# linetracer.net
KiCad netlist of a schematic drawn in EAGLE
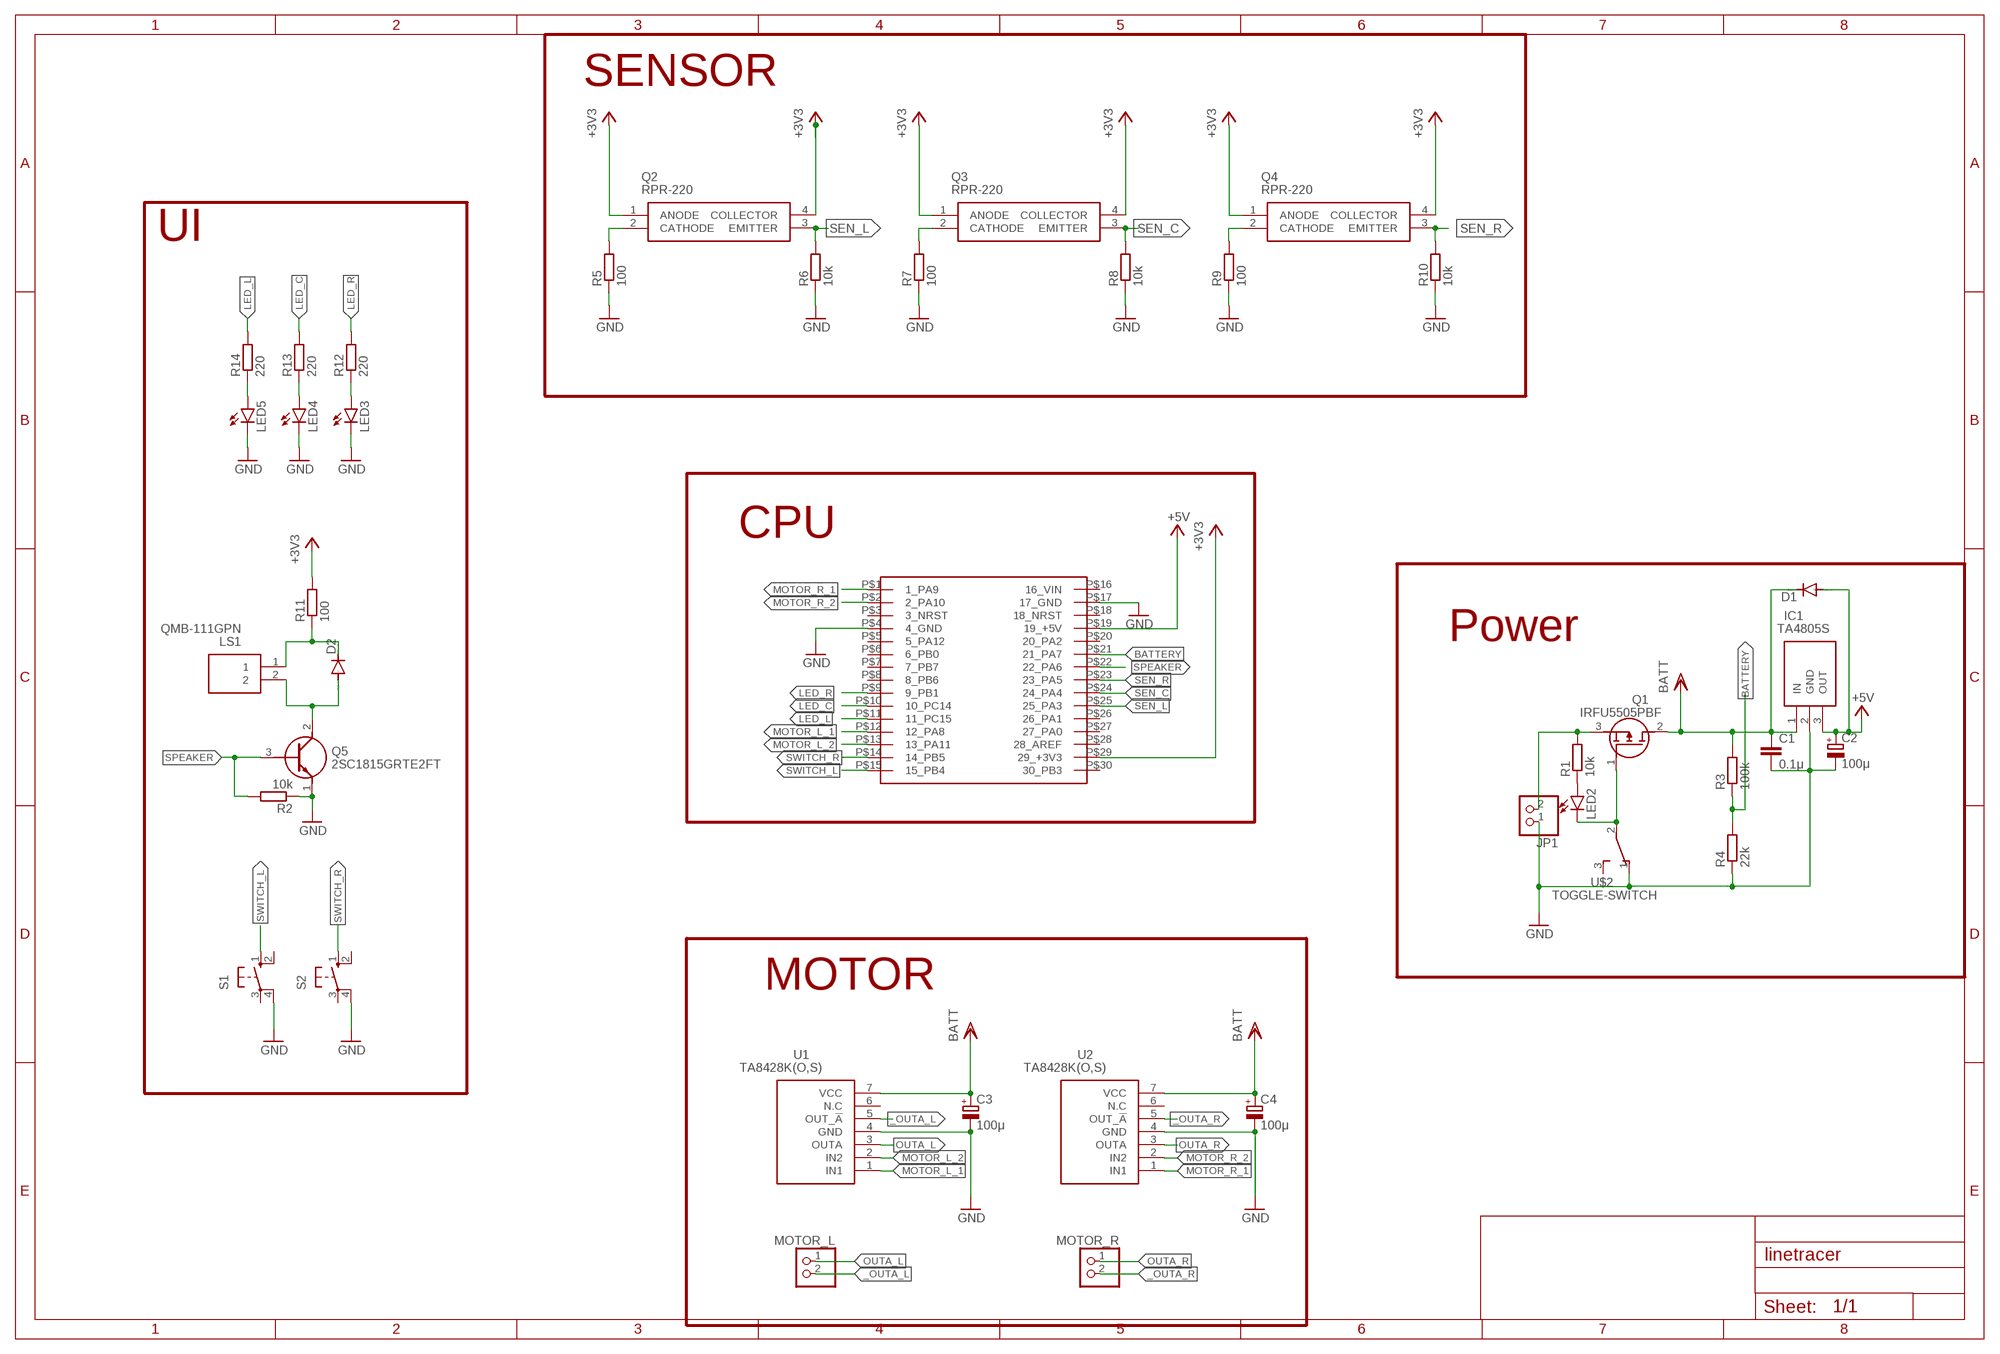
[diagram p0: schematic, sheet 1]

(export (version "E")
  (design (tool "Eeschema 10.0.6"))
  (components
    (comp (ref "C1")
      (value "0.1μ")
      (footprint "eagle-import:C025-024X044")
      (libsource (lib "eagle-import") (part "C-EU025-024X044"))
    )
    (comp (ref "C2")
      (value "100μ")
      (footprint "eagle-import:E2,5-7")
      (libsource (lib "eagle-import") (part "CPOL-EUE2.5-7"))
    )
    (comp (ref "C3")
      (value "100μ")
      (footprint "eagle-import:E2,5-7")
      (libsource (lib "eagle-import") (part "CPOL-EUE2.5-7"))
    )
    (comp (ref "C4")
      (value "100μ")
      (footprint "eagle-import:E2,5-7")
      (libsource (lib "eagle-import") (part "CPOL-EUE2.5-7"))
    )
    (comp (ref "D1")
      (value "DIODE-D-2.5")
      (footprint "eagle-import:D-2.5")
      (libsource (lib "eagle-import") (part "DIODE-D-2.5"))
    )
    (comp (ref "D2")
      (value "DIODE-D-2.5")
      (footprint "eagle-import:D-2.5")
      (libsource (lib "eagle-import") (part "DIODE-D-2.5"))
    )
    (comp (ref "IC1")
      (value "TA4805S")
      (footprint "eagle-import:TO230P250X680X1080-3P")
      (fields (field (name "MANUFACTURER_PART_NUMBER") "TA4805F"))
      (libsource (lib "eagle-import") (part "TA4805S"))
    )
    (comp (ref "JP1")
      (value "PINHD-1X2")
      (footprint "eagle-import:1X02")
      (libsource (lib "eagle-import") (part "PINHD-1X2"))
    )
    (comp (ref "LED2")
      (value "LED3MM")
      (footprint "eagle-import:LED3MM")
      (libsource (lib "eagle-import") (part "LED3MM"))
    )
    (comp (ref "LED3")
      (value "LED3MM")
      (footprint "eagle-import:LED3MM")
      (libsource (lib "eagle-import") (part "LED3MM"))
    )
    (comp (ref "LED4")
      (value "LED3MM")
      (footprint "eagle-import:LED3MM")
      (libsource (lib "eagle-import") (part "LED3MM"))
    )
    (comp (ref "LED5")
      (value "LED3MM")
      (footprint "eagle-import:LED3MM")
      (libsource (lib "eagle-import") (part "LED3MM"))
    )
    (comp (ref "LS1")
      (value "QMB-111GPN")
      (footprint "eagle-import:QMB111GPN")
      (libsource (lib "eagle-import") (part "QMB-111GPN"))
    )
    (comp (ref "MOTOR_L")
      (value "PINHD-1X2")
      (footprint "eagle-import:1X02")
      (libsource (lib "eagle-import") (part "pinhead_325_PINHD-1X2"))
    )
    (comp (ref "MOTOR_R")
      (value "PINHD-1X2")
      (footprint "eagle-import:1X02")
      (libsource (lib "eagle-import") (part "pinhead_325_PINHD-1X2"))
    )
    (comp (ref "Q1")
      (value "IRFU5505PBF")
      (footprint "eagle-import:TO229P239X654X978-3P")
      (fields (field (name "MOUSER_PART_NUMBER") "942-IRFU5505PBF"))
      (libsource (lib "eagle-import") (part "IRFU5505PBF"))
    )
    (comp (ref "Q2")
      (value "RPR-220")
      (footprint "eagle-import:RPR-220")
      (fields (field (name "MOUSER_PART_NUMBER") "755-RPR-220") (field (name "RS_PART_NUMBER") "1246800P"))
      (libsource (lib "eagle-import") (part "RPR-220"))
    )
    (comp (ref "Q3")
      (value "RPR-220")
      (footprint "eagle-import:RPR-220")
      (fields (field (name "MOUSER_PART_NUMBER") "755-RPR-220") (field (name "RS_PART_NUMBER") "1246800P"))
      (libsource (lib "eagle-import") (part "RPR-220"))
    )
    (comp (ref "Q4")
      (value "RPR-220")
      (footprint "eagle-import:RPR-220")
      (fields (field (name "MOUSER_PART_NUMBER") "755-RPR-220") (field (name "RS_PART_NUMBER") "1246800P"))
      (libsource (lib "eagle-import") (part "RPR-220"))
    )
    (comp (ref "Q5")
      (value "2SC1815GRTE2FT")
      (footprint "eagle-import:2-5F1B")
      (fields (field (name "MOUSER_PART_NUMBER") "757-2SC1815GRTE2FT"))
      (libsource (lib "eagle-import") (part "2SC1815GRTE2FT"))
    )
    (comp (ref "R1")
      (value "10k")
      (footprint "eagle-import:0204V")
      (libsource (lib "eagle-import") (part "R-EU_0204/2V"))
    )
    (comp (ref "R2")
      (value "10k")
      (footprint "eagle-import:0204V")
      (libsource (lib "eagle-import") (part "R-EU_0204/2V"))
    )
    (comp (ref "R3")
      (value "100k")
      (footprint "eagle-import:0204V")
      (libsource (lib "eagle-import") (part "R-EU_0204/2V"))
    )
    (comp (ref "R4")
      (value "22k")
      (footprint "eagle-import:0204V")
      (libsource (lib "eagle-import") (part "R-EU_0204/2V"))
    )
    (comp (ref "R5")
      (value "100")
      (footprint "eagle-import:0204V")
      (libsource (lib "eagle-import") (part "R-EU_0204/2V"))
    )
    (comp (ref "R6")
      (value "10k")
      (footprint "eagle-import:0204V")
      (libsource (lib "eagle-import") (part "R-EU_0204/2V"))
    )
    (comp (ref "R7")
      (value "100")
      (footprint "eagle-import:0204V")
      (libsource (lib "eagle-import") (part "R-EU_0204/2V"))
    )
    (comp (ref "R8")
      (value "10k")
      (footprint "eagle-import:0204V")
      (libsource (lib "eagle-import") (part "R-EU_0204/2V"))
    )
    (comp (ref "R9")
      (value "100")
      (footprint "eagle-import:0204V")
      (libsource (lib "eagle-import") (part "R-EU_0204/2V"))
    )
    (comp (ref "R10")
      (value "10k")
      (footprint "eagle-import:0204V")
      (libsource (lib "eagle-import") (part "R-EU_0204/2V"))
    )
    (comp (ref "R11")
      (value "100")
      (footprint "eagle-import:0204V")
      (libsource (lib "eagle-import") (part "R-EU_0204/2V"))
    )
    (comp (ref "R12")
      (value "220")
      (footprint "eagle-import:0204V")
      (libsource (lib "eagle-import") (part "R-EU_0204/2V"))
    )
    (comp (ref "R13")
      (value "220")
      (footprint "eagle-import:0204V")
      (libsource (lib "eagle-import") (part "R-EU_0204/2V"))
    )
    (comp (ref "R14")
      (value "220")
      (footprint "eagle-import:0204V")
      (libsource (lib "eagle-import") (part "R-EU_0204/2V"))
    )
    (comp (ref "S1")
      (value "10-XX")
      (footprint "eagle-import:B3F-10XX")
      (fields (field (name "MPN") "B3F-1000"))
      (libsource (lib "eagle-import") (part "10-XX"))
    )
    (comp (ref "S2")
      (value "10-XX")
      (footprint "eagle-import:B3F-10XX")
      (fields (field (name "MPN") "B3F-1000"))
      (libsource (lib "eagle-import") (part "10-XX"))
    )
    (comp (ref "U$1")
      (value "NUCLEO_L432KC")
      (footprint "eagle-import:NUCLEO_L432KC")
      (libsource (lib "eagle-import") (part "NUCLEO_L432KC"))
    )
    (comp (ref "U$2")
      (value "TOGGLE-SWITCH")
      (footprint "eagle-import:1X03")
      (libsource (lib "eagle-import") (part "TOGGLE-SWITCH"))
    )
    (comp (ref "U1")
      (value "TA8428K(O,S)")
      (footprint "eagle-import:HSIP7-P-2.54_1")
      (fields (field (name "MOUSER_PART_NUMBER") "757-TA8428KOS") (field (name "RS_PART_NUMBER") "6939336"))
      (libsource (lib "eagle-import") (part "TA8428K(O,S)"))
    )
    (comp (ref "U2")
      (value "TA8428K(O,S)")
      (footprint "eagle-import:HSIP7-P-2.54_1")
      (fields (field (name "MOUSER_PART_NUMBER") "757-TA8428KOS") (field (name "RS_PART_NUMBER") "6939336"))
      (libsource (lib "eagle-import") (part "TA8428K(O,S)"))
    )
  )
  (nets
    (net (code "1") (name "+3V3") (class "Default")
      (node (ref "Q2") (pin "1") (pinfunction "ANODE_1") (pintype "bidirectional"))
      (node (ref "Q2") (pin "4") (pinfunction "COLLECTOR_4") (pintype "bidirectional"))
      (node (ref "Q3") (pin "1") (pinfunction "ANODE_1") (pintype "bidirectional"))
      (node (ref "Q3") (pin "4") (pinfunction "COLLECTOR_4") (pintype "bidirectional"))
      (node (ref "Q4") (pin "1") (pinfunction "ANODE_1") (pintype "bidirectional"))
      (node (ref "Q4") (pin "4") (pinfunction "COLLECTOR_4") (pintype "bidirectional"))
      (node (ref "R11") (pin "2") (pinfunction "2_2") (pintype "passive"))
      (node (ref "U$1") (pin "P$29") (pinfunction "29_+3V3_P$29") (pintype "power_in"))
    )
    (net (code "2") (name "+5V") (class "Default")
      (node (ref "C2") (pin "+") (pinfunction "+_+") (pintype "passive"))
      (node (ref "D1") (pin "A") (pinfunction "A_A") (pintype "passive"))
      (node (ref "IC1") (pin "3") (pinfunction "OUT_3") (pintype "bidirectional"))
      (node (ref "U$1") (pin "P$19") (pinfunction "19_+5V_P$19") (pintype "power_in"))
    )
    (net (code "3") (name "/16_VIN") (class "Default")
      (node (ref "U$1") (pin "P$16") (pinfunction "16_VIN_P$16") (pintype "power_in"))
    )
    (net (code "4") (name "BATT") (class "Default")
      (node (ref "C1") (pin "1") (pinfunction "1_1") (pintype "passive"))
      (node (ref "C3") (pin "+") (pinfunction "+_+") (pintype "passive"))
      (node (ref "C4") (pin "+") (pinfunction "+_+") (pintype "passive"))
      (node (ref "D1") (pin "C") (pinfunction "C_C") (pintype "passive"))
      (node (ref "IC1") (pin "1") (pinfunction "IN_1") (pintype "bidirectional"))
      (node (ref "Q1") (pin "2") (pinfunction "D_2") (pintype "bidirectional"))
      (node (ref "R3") (pin "2") (pinfunction "2_2") (pintype "passive"))
      (node (ref "U1") (pin "7") (pinfunction "VCC_7") (pintype "bidirectional"))
      (node (ref "U2") (pin "7") (pinfunction "VCC_7") (pintype "bidirectional"))
    )
    (net (code "5") (name "BATTERY") (class "Default")
      (node (ref "R3") (pin "1") (pinfunction "1_1") (pintype "passive"))
      (node (ref "R4") (pin "2") (pinfunction "2_2") (pintype "passive"))
      (node (ref "U$1") (pin "P$21") (pinfunction "21_PA7_P$21") (pintype "bidirectional"))
    )
    (net (code "6") (name "GND") (class "Default")
      (node (ref "C1") (pin "2") (pinfunction "2_2") (pintype "passive"))
      (node (ref "C2") (pin "-") (pinfunction "-_-") (pintype "passive"))
      (node (ref "C3") (pin "-") (pinfunction "-_-") (pintype "passive"))
      (node (ref "C4") (pin "-") (pinfunction "-_-") (pintype "passive"))
      (node (ref "IC1") (pin "2") (pinfunction "GND_2") (pintype "bidirectional"))
      (node (ref "JP1") (pin "1") (pinfunction "1_1") (pintype "passive"))
      (node (ref "LED3") (pin "K") (pinfunction "C_K") (pintype "passive"))
      (node (ref "LED4") (pin "K") (pinfunction "C_K") (pintype "passive"))
      (node (ref "LED5") (pin "K") (pinfunction "C_K") (pintype "passive"))
      (node (ref "Q5") (pin "1") (pinfunction "E_1") (pintype "bidirectional"))
      (node (ref "R10") (pin "1") (pinfunction "1_1") (pintype "passive"))
      (node (ref "R2") (pin "1") (pinfunction "1_1") (pintype "passive"))
      (node (ref "R4") (pin "1") (pinfunction "1_1") (pintype "passive"))
      (node (ref "R5") (pin "1") (pinfunction "1_1") (pintype "passive"))
      (node (ref "R6") (pin "1") (pinfunction "1_1") (pintype "passive"))
      (node (ref "R7") (pin "1") (pinfunction "1_1") (pintype "passive"))
      (node (ref "R8") (pin "1") (pinfunction "1_1") (pintype "passive"))
      (node (ref "R9") (pin "1") (pinfunction "1_1") (pintype "passive"))
      (node (ref "S1") (pin "4") (pinfunction "P1_4") (pintype "passive"))
      (node (ref "S2") (pin "4") (pinfunction "P1_4") (pintype "passive"))
      (node (ref "U$1") (pin "P$17") (pinfunction "17_GND_P$17") (pintype "power_in"))
      (node (ref "U$1") (pin "P$4") (pinfunction "4_GND_P$4") (pintype "power_in"))
      (node (ref "U$2") (pin "1") (pinfunction "1_1") (pintype "power_in"))
      (node (ref "U1") (pin "4") (pinfunction "GND_4") (pintype "bidirectional"))
      (node (ref "U2") (pin "4") (pinfunction "GND_4") (pintype "bidirectional"))
    )
    (net (code "7") (name "LED_C") (class "Default")
      (node (ref "R13") (pin "2") (pinfunction "2_2") (pintype "passive"))
      (node (ref "U$1") (pin "P$10") (pinfunction "10_PC14_P$10") (pintype "bidirectional"))
    )
    (net (code "8") (name "LED_L") (class "Default")
      (node (ref "R14") (pin "2") (pinfunction "2_2") (pintype "passive"))
      (node (ref "U$1") (pin "P$11") (pinfunction "11_PC15_P$11") (pintype "bidirectional"))
    )
    (net (code "9") (name "LED_R") (class "Default")
      (node (ref "R12") (pin "2") (pinfunction "2_2") (pintype "passive"))
      (node (ref "U$1") (pin "P$9") (pinfunction "9_PB1_P$9") (pintype "bidirectional"))
    )
    (net (code "10") (name "MOTOR_L_1") (class "Default")
      (node (ref "U$1") (pin "P$12") (pinfunction "12_PA8_P$12") (pintype "bidirectional"))
      (node (ref "U1") (pin "1") (pinfunction "IN1_1") (pintype "bidirectional"))
    )
    (net (code "11") (name "MOTOR_L_2") (class "Default")
      (node (ref "U$1") (pin "P$13") (pinfunction "13_PA11_P$13") (pintype "bidirectional"))
      (node (ref "U1") (pin "2") (pinfunction "IN2_2") (pintype "bidirectional"))
    )
    (net (code "12") (name "MOTOR_R_1") (class "Default")
      (node (ref "U$1") (pin "P$1") (pinfunction "1_PA9_P$1") (pintype "bidirectional"))
      (node (ref "U2") (pin "1") (pinfunction "IN1_1") (pintype "bidirectional"))
    )
    (net (code "13") (name "MOTOR_R_2") (class "Default")
      (node (ref "U$1") (pin "P$2") (pinfunction "2_PA10_P$2") (pintype "bidirectional"))
      (node (ref "U2") (pin "2") (pinfunction "IN2_2") (pintype "bidirectional"))
    )
    (net (code "14") (name "Net-(D2-PadC)") (class "Default")
      (node (ref "D2") (pin "C") (pinfunction "C_C") (pintype "passive"))
      (node (ref "LS1") (pin "1") (pinfunction "1_1") (pintype "bidirectional"))
      (node (ref "R11") (pin "1") (pinfunction "1_1") (pintype "passive"))
    )
    (net (code "15") (name "Net-(LED2-C)") (class "Default")
      (node (ref "LED2") (pin "K") (pinfunction "C_K") (pintype "passive"))
      (node (ref "Q1") (pin "1") (pinfunction "G_1") (pintype "bidirectional"))
      (node (ref "U$2") (pin "2") (pinfunction "2_2") (pintype "passive"))
    )
    (net (code "16") (name "Net-(LED2-PadA)") (class "Default")
      (node (ref "LED2") (pin "A") (pinfunction "A_A") (pintype "passive"))
      (node (ref "R1") (pin "1") (pinfunction "1_1") (pintype "passive"))
    )
    (net (code "17") (name "Net-(LED3-PadA)") (class "Default")
      (node (ref "LED3") (pin "A") (pinfunction "A_A") (pintype "passive"))
      (node (ref "R12") (pin "1") (pinfunction "1_1") (pintype "passive"))
    )
    (net (code "18") (name "Net-(LED4-PadA)") (class "Default")
      (node (ref "LED4") (pin "A") (pinfunction "A_A") (pintype "passive"))
      (node (ref "R13") (pin "1") (pinfunction "1_1") (pintype "passive"))
    )
    (net (code "19") (name "Net-(LED5-PadA)") (class "Default")
      (node (ref "LED5") (pin "A") (pinfunction "A_A") (pintype "passive"))
      (node (ref "R14") (pin "1") (pinfunction "1_1") (pintype "passive"))
    )
    (net (code "20") (name "Net-(Q1-S)") (class "Default")
      (node (ref "JP1") (pin "2") (pinfunction "2_2") (pintype "passive"))
      (node (ref "Q1") (pin "3") (pinfunction "S_3") (pintype "bidirectional"))
      (node (ref "R1") (pin "2") (pinfunction "2_2") (pintype "passive"))
    )
    (net (code "21") (name "Net-(Q2-CATHODE)") (class "Default")
      (node (ref "Q2") (pin "2") (pinfunction "CATHODE_2") (pintype "bidirectional"))
      (node (ref "R5") (pin "2") (pinfunction "2_2") (pintype "passive"))
    )
    (net (code "22") (name "Net-(Q3-CATHODE)") (class "Default")
      (node (ref "Q3") (pin "2") (pinfunction "CATHODE_2") (pintype "bidirectional"))
      (node (ref "R7") (pin "2") (pinfunction "2_2") (pintype "passive"))
    )
    (net (code "23") (name "Net-(Q4-CATHODE)") (class "Default")
      (node (ref "Q4") (pin "2") (pinfunction "CATHODE_2") (pintype "bidirectional"))
      (node (ref "R9") (pin "2") (pinfunction "2_2") (pintype "passive"))
    )
    (net (code "24") (name "Net-(Q5-C)") (class "Default")
      (node (ref "D2") (pin "A") (pinfunction "A_A") (pintype "passive"))
      (node (ref "LS1") (pin "2") (pinfunction "2_2") (pintype "bidirectional"))
      (node (ref "Q5") (pin "2") (pinfunction "C_2") (pintype "bidirectional"))
    )
    (net (code "25") (name "OUTA_L") (class "Default")
      (node (ref "MOTOR_L") (pin "1") (pinfunction "1_1") (pintype "passive"))
      (node (ref "U1") (pin "3") (pinfunction "OUTA_3") (pintype "bidirectional"))
    )
    (net (code "26") (name "OUTA_R") (class "Default")
      (node (ref "MOTOR_R") (pin "1") (pinfunction "1_1") (pintype "passive"))
      (node (ref "U2") (pin "3") (pinfunction "OUTA_3") (pintype "bidirectional"))
    )
    (net (code "27") (name "SEN_C") (class "Default")
      (node (ref "Q3") (pin "3") (pinfunction "EMITTER_3") (pintype "bidirectional"))
      (node (ref "R8") (pin "2") (pinfunction "2_2") (pintype "passive"))
      (node (ref "U$1") (pin "P$24") (pinfunction "24_PA4_P$24") (pintype "bidirectional"))
    )
    (net (code "28") (name "SEN_L") (class "Default")
      (node (ref "Q2") (pin "3") (pinfunction "EMITTER_3") (pintype "bidirectional"))
      (node (ref "R6") (pin "2") (pinfunction "2_2") (pintype "passive"))
      (node (ref "U$1") (pin "P$25") (pinfunction "25_PA3_P$25") (pintype "bidirectional"))
    )
    (net (code "29") (name "SEN_R") (class "Default")
      (node (ref "Q4") (pin "3") (pinfunction "EMITTER_3") (pintype "bidirectional"))
      (node (ref "R10") (pin "2") (pinfunction "2_2") (pintype "passive"))
      (node (ref "U$1") (pin "P$23") (pinfunction "23_PA5_P$23") (pintype "bidirectional"))
    )
    (net (code "30") (name "SPEAKER") (class "Default")
      (node (ref "Q5") (pin "3") (pinfunction "B_3") (pintype "bidirectional"))
      (node (ref "R2") (pin "2") (pinfunction "2_2") (pintype "passive"))
      (node (ref "U$1") (pin "P$22") (pinfunction "22_PA6_P$22") (pintype "bidirectional"))
    )
    (net (code "31") (name "SWITCH_L") (class "Default")
      (node (ref "S1") (pin "1") (pinfunction "S_1") (pintype "passive"))
      (node (ref "U$1") (pin "P$15") (pinfunction "15_PB4_P$15") (pintype "bidirectional"))
    )
    (net (code "32") (name "SWITCH_R") (class "Default")
      (node (ref "S2") (pin "1") (pinfunction "S_1") (pintype "passive"))
      (node (ref "U$1") (pin "P$14") (pinfunction "14_PB5_P$14") (pintype "bidirectional"))
    )
    (net (code "33") (name "_OUTA_L") (class "Default")
      (node (ref "MOTOR_L") (pin "2") (pinfunction "2_2") (pintype "passive"))
      (node (ref "U1") (pin "5") (pinfunction "OUT_~{A}_5") (pintype "bidirectional"))
    )
    (net (code "34") (name "_OUTA_R") (class "Default")
      (node (ref "MOTOR_R") (pin "2") (pinfunction "2_2") (pintype "passive"))
      (node (ref "U2") (pin "5") (pinfunction "OUT_~{A}_5") (pintype "bidirectional"))
    )
    (net (code "35") (name "unconnected-(S1-P-Pad3)") (class "Default")
      (node (ref "S1") (pin "3") (pinfunction "P_3") (pintype "passive"))
    )
    (net (code "36") (name "unconnected-(S1-S1-Pad2)") (class "Default")
      (node (ref "S1") (pin "2") (pinfunction "S1_2") (pintype "passive"))
    )
    (net (code "37") (name "unconnected-(S2-P-Pad3)") (class "Default")
      (node (ref "S2") (pin "3") (pinfunction "P_3") (pintype "passive"))
    )
    (net (code "38") (name "unconnected-(S2-S1-Pad2)") (class "Default")
      (node (ref "S2") (pin "2") (pinfunction "S1_2") (pintype "passive"))
    )
    (net (code "39") (name "unconnected-(U$1-3_NRST-PadP$3)") (class "Default")
      (node (ref "U$1") (pin "P$3") (pinfunction "3_NRST_P$3") (pintype "bidirectional"))
    )
    (net (code "40") (name "unconnected-(U$1-5_PA12-PadP$5)") (class "Default")
      (node (ref "U$1") (pin "P$5") (pinfunction "5_PA12_P$5") (pintype "bidirectional"))
    )
    (net (code "41") (name "unconnected-(U$1-6_PB0-PadP$6)") (class "Default")
      (node (ref "U$1") (pin "P$6") (pinfunction "6_PB0_P$6") (pintype "bidirectional"))
    )
    (net (code "42") (name "unconnected-(U$1-7_PB7-PadP$7)") (class "Default")
      (node (ref "U$1") (pin "P$7") (pinfunction "7_PB7_P$7") (pintype "bidirectional"))
    )
    (net (code "43") (name "unconnected-(U$1-8_PB6-PadP$8)") (class "Default")
      (node (ref "U$1") (pin "P$8") (pinfunction "8_PB6_P$8") (pintype "bidirectional"))
    )
    (net (code "44") (name "unconnected-(U$1-18_NRST-PadP$18)") (class "Default")
      (node (ref "U$1") (pin "P$18") (pinfunction "18_NRST_P$18") (pintype "bidirectional"))
    )
    (net (code "45") (name "unconnected-(U$1-20_PA2-PadP$20)") (class "Default")
      (node (ref "U$1") (pin "P$20") (pinfunction "20_PA2_P$20") (pintype "bidirectional"))
    )
    (net (code "46") (name "unconnected-(U$1-26_PA1-PadP$26)") (class "Default")
      (node (ref "U$1") (pin "P$26") (pinfunction "26_PA1_P$26") (pintype "bidirectional"))
    )
    (net (code "47") (name "unconnected-(U$1-27_PA0-PadP$27)") (class "Default")
      (node (ref "U$1") (pin "P$27") (pinfunction "27_PA0_P$27") (pintype "bidirectional"))
    )
    (net (code "48") (name "unconnected-(U$1-28_AREF-PadP$28)") (class "Default")
      (node (ref "U$1") (pin "P$28") (pinfunction "28_AREF_P$28") (pintype "bidirectional"))
    )
    (net (code "49") (name "unconnected-(U$1-30_PB3-PadP$30)") (class "Default")
      (node (ref "U$1") (pin "P$30") (pinfunction "30_PB3_P$30") (pintype "bidirectional"))
    )
    (net (code "50") (name "unconnected-(U$2-Pad3)") (class "Default")
      (node (ref "U$2") (pin "3") (pinfunction "3_3") (pintype "passive"))
    )
    (net (code "51") (name "unconnected-(U1-N.C-Pad6)") (class "Default")
      (node (ref "U1") (pin "6") (pinfunction "N.C_6") (pintype "no_connect"))
    )
    (net (code "52") (name "unconnected-(U2-N.C-Pad6)") (class "Default")
      (node (ref "U2") (pin "6") (pinfunction "N.C_6") (pintype "no_connect"))
    )
  )
)
